# LEO_COTS_ant_tripler_rev1.net
KiCad netlist of a schematic drawn in Altium Designer
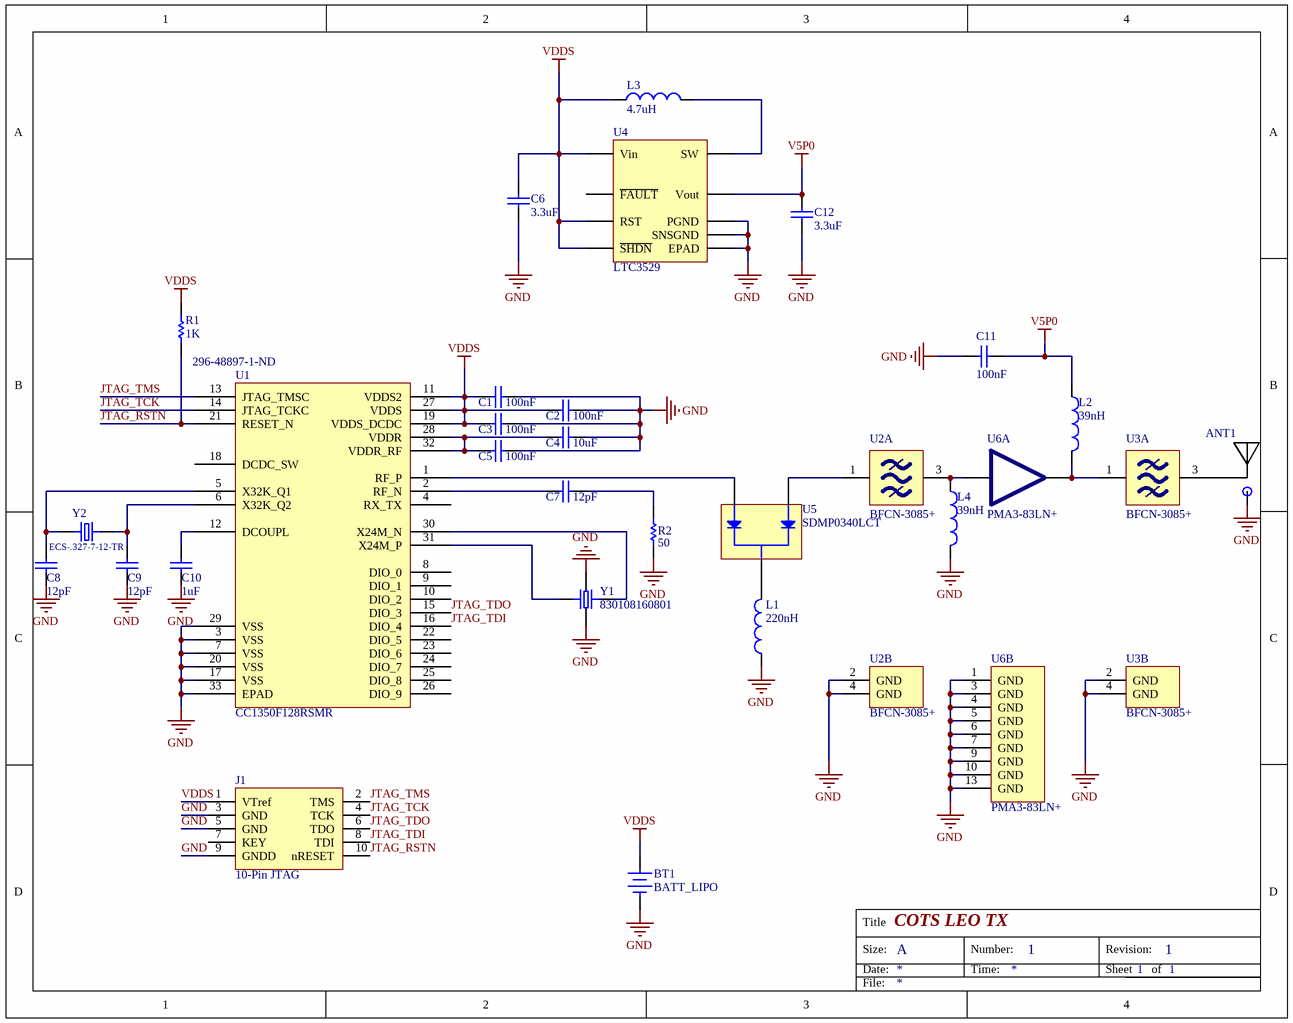
[diagram p0: LEO_COTS_ant_tripler_rev1.SchDoc]

(export (version "E")
  (design (tool "Eeschema 10.0.6"))
  (components
    (comp (ref "ANT1")
      (value "ANT")
      (footprint "RESLOOP_OD10_fw15_fl180_sw12_sl15")
      (description "PCB antenna")
      (libsource (lib "LEO_COTS_components") (part "ANT"))
    )
    (comp (ref "BT1")
      (value "BATT_LIPO")
      (footprint "LIPO_1cm_1cm")
      (libsource (lib "LEO_COTS_components") (part "BATT_LIPO"))
    )
    (comp (ref "C1")
      (value "100nF")
      (footprint "CAPC0603X04N")
      (description "CAP CER 100nF 0201")
      (fields (field (name "Comment") "CAP_0201"))
      (libsource (lib "LEO_COTS_components") (part "CAP_0201"))
    )
    (comp (ref "C2")
      (value "100nF")
      (footprint "CAPC0603X04N")
      (description "CAP CER 100nF 0201")
      (fields (field (name "Comment") "CAP_0201"))
      (libsource (lib "LEO_COTS_components") (part "CAP_0201"))
    )
    (comp (ref "C3")
      (value "100nF")
      (footprint "CAPC0603X04N")
      (description "CAP CER 100nF 0201")
      (fields (field (name "Comment") "CAP_0201"))
      (libsource (lib "LEO_COTS_components") (part "CAP_0201"))
    )
    (comp (ref "C4")
      (value "10uF")
      (footprint "CAPC1608X05N")
      (description "CAP CER 10uF 0603")
      (fields (field (name "Comment") "CAP_0603"))
      (libsource (lib "LEO_COTS_components") (part "CAP_0603"))
    )
    (comp (ref "C5")
      (value "100nF")
      (footprint "CAPC0603X04N")
      (description "CAP CER 100nF 0201")
      (fields (field (name "Comment") "CAP_0201"))
      (libsource (lib "LEO_COTS_components") (part "CAP_0201"))
    )
    (comp (ref "C6")
      (value "3.3uF")
      (footprint "CAPC1608X05N")
      (description "CAP CER 3.3uF 0603")
      (fields (field (name "Comment") "CAP_0603"))
      (libsource (lib "LEO_COTS_components") (part "CAP_0603"))
    )
    (comp (ref "C7")
      (value "12pF")
      (footprint "CAPC0603X04N")
      (description "CAP CER 12pF 0201")
      (fields (field (name "Comment") "CAP_0201"))
      (libsource (lib "LEO_COTS_components") (part "CAP_0201"))
    )
    (comp (ref "C8")
      (value "12pF")
      (footprint "CAPC0603X04N")
      (description "CAP CER 12pF 0201")
      (fields (field (name "Comment") "CAP_0201"))
      (libsource (lib "LEO_COTS_components") (part "CAP_0201"))
    )
    (comp (ref "C9")
      (value "12pF")
      (footprint "CAPC0603X04N")
      (description "CAP CER 12pF 0201")
      (fields (field (name "Comment") "CAP_0201"))
      (libsource (lib "LEO_COTS_components") (part "CAP_0201"))
    )
    (comp (ref "C10")
      (value "1uF")
      (footprint "CAPC0603X04N")
      (description "CAP CER 1uF 0201")
      (fields (field (name "Comment") "CAP_0201"))
      (libsource (lib "LEO_COTS_components") (part "CAP_0201"))
    )
    (comp (ref "C11")
      (value "100nF")
      (footprint "CAPC0603X04N")
      (description "CAP CER 100nF 0201")
      (fields (field (name "Comment") "CAP_0201"))
      (libsource (lib "LEO_COTS_components") (part "CAP_0201"))
    )
    (comp (ref "C12")
      (value "3.3uF")
      (footprint "CAPC1608X05N")
      (description "CAP CER 3.3uF 0603")
      (fields (field (name "Comment") "CAP_0603"))
      (libsource (lib "LEO_COTS_components") (part "CAP_0603"))
    )
    (comp (ref "J1")
      (value "10-Pin JTAG")
      (footprint "FTSH-105-01-F-DV-007-K")
      (description "10-pin JTAG")
      (libsource (lib "LEO_COTS_components") (part "CM10"))
    )
    (comp (ref "L1")
      (value "220nH")
      (footprint "0402")
      (description "Inductor")
      (fields (field (name "PUBLISHER") "Altium Limited"))
      (libsource (lib "") (part "Inductor_1"))
    )
    (comp (ref "L2")
      (value "39nH")
      (footprint "0402")
      (description "Inductor")
      (fields (field (name "PUBLISHER") "Altium Limited"))
      (libsource (lib "LEO_COTS_components") (part "Inductor"))
    )
    (comp (ref "L3")
      (value "4.7uH")
      (footprint "C0805")
      (description "Inductor")
      (fields (field (name "PUBLISHER") "Altium Limited"))
      (libsource (lib "LEO_COTS_components") (part "Inductor"))
    )
    (comp (ref "L4")
      (value "39nH")
      (footprint "0402")
      (description "Inductor")
      (fields (field (name "PUBLISHER") "Altium Limited"))
      (libsource (lib "LEO_COTS_components") (part "Inductor"))
    )
    (comp (ref "R1")
      (value "1K")
      (footprint "CAPC0603X04N")
      (description "RES 1K OHM 0201")
      (fields (field (name "Comment") "RES_0201") (field (name "PUBLISHER") "Altium Limited"))
      (libsource (lib "LEO_COTS_components") (part "Res Semi"))
    )
    (comp (ref "R2")
      (value "50")
      (footprint "CAPC0603X04N")
      (description "RES 50 OHM 0201")
      (fields (field (name "Comment") "RES_0201") (field (name "PUBLISHER") "Altium Limited"))
      (libsource (lib "LEO_COTS_components") (part "Res Semi"))
    )
    (comp (ref "U1")
      (value "CC1350F128RSMR")
      (footprint "QFN40P400X400X100-33N")
      (description "Ultra-Low-Power Dual-Band Wireless MCU")
      (fields (field (name "SUPPLIER PART NUMBER 1") "296-48897-1-ND"))
      (libsource (lib "LEO_COTS_components") (part "CC1350F128RSMR"))
    )
    (comp (ref "U2")
      (value "BFCN-3085+")
      (footprint "FV1206")
      (description "2800 to 3400 MHz Band-Pass Filter")
      (libsource (lib "LEO_COTS_components") (part "BFCN-3085+"))
    )
    (comp (ref "U3")
      (value "BFCN-3085+")
      (footprint "FV1206")
      (description "2800 to 3400 MHz Band-Pass Filter")
      (libsource (lib "LEO_COTS_components") (part "BFCN-3085+"))
    )
    (comp (ref "U4")
      (value "LTC3529")
      (footprint "8-DFN")
      (description "5V Boost Converter")
      (libsource (lib "LEO_COTS_components") (part "LTC3529"))
    )
    (comp (ref "U5")
      (value "SDMP0340LCT")
      (footprint "SOT-523")
      (description "Dual Common Cathode Schottky")
      (libsource (lib "LEO_COTS_components") (part "SDMP0340LCT"))
    )
    (comp (ref "U6")
      (value "PMA3-83LN+")
      (footprint "DQ1225")
      (description "Wideband LNA")
      (libsource (lib "LEO_COTS_components") (part "PMA3-83LN+"))
    )
    (comp (ref "Y1")
      (value "830108160801")
      (footprint "LFXTAL081608")
      (description "24 MHz crystal")
      (libsource (lib "LEO_COTS_components") (part "830108160801"))
    )
    (comp (ref "Y2")
      (value "ECS-.327-7-12-TR")
      (footprint "XTAL_ECS-.327-7-12-TR")
      (description "32.768 kHz SMD Crystal")
      (libsource (lib "LEO_COTS_components") (part "ECS-.327-7-12-TR"))
    )
  )
  (nets
    (net (code "1") (name "/JTAG_RSTN") (class "Default")
      (node (ref "J1") (pin "10") (pinfunction "nRESET_10") (pintype "passive"))
      (node (ref "R1") (pin "1") (pinfunction "1_1") (pintype "passive"))
      (node (ref "U1") (pin "21") (pinfunction "RESET_N_21") (pintype "passive"))
    )
    (net (code "2") (name "/JTAG_TCK") (class "Default")
      (node (ref "J1") (pin "4") (pinfunction "TCK_4") (pintype "passive"))
      (node (ref "U1") (pin "14") (pinfunction "JTAG_TCKC_14") (pintype "passive"))
    )
    (net (code "3") (name "/JTAG_TDI") (class "Default")
      (node (ref "J1") (pin "8") (pinfunction "TDI_8") (pintype "passive"))
      (node (ref "U1") (pin "16") (pinfunction "DIO_4_16") (pintype "passive"))
    )
    (net (code "4") (name "/JTAG_TDO") (class "Default")
      (node (ref "J1") (pin "6") (pinfunction "TDO_6") (pintype "passive"))
      (node (ref "U1") (pin "15") (pinfunction "DIO_3_15") (pintype "passive"))
    )
    (net (code "5") (name "/JTAG_TMS") (class "Default")
      (node (ref "J1") (pin "2") (pinfunction "TMS_2") (pintype "passive"))
      (node (ref "U1") (pin "13") (pinfunction "JTAG_TMSC_13") (pintype "passive"))
    )
    (net (code "6") (name "GND") (class "Default")
      (node (ref "ANT1") (pin "2") (pinfunction "-_2") (pintype "passive"))
      (node (ref "BT1") (pin "2") (pinfunction "-_2") (pintype "passive"))
      (node (ref "C1") (pin "1") (pinfunction "1_1") (pintype "passive"))
      (node (ref "C10") (pin "1") (pinfunction "1_1") (pintype "passive"))
      (node (ref "C11") (pin "1") (pinfunction "1_1") (pintype "passive"))
      (node (ref "C12") (pin "1") (pinfunction "1_1") (pintype "passive"))
      (node (ref "C2") (pin "1") (pinfunction "1_1") (pintype "passive"))
      (node (ref "C3") (pin "1") (pinfunction "1_1") (pintype "passive"))
      (node (ref "C4") (pin "2") (pinfunction "2_2") (pintype "passive"))
      (node (ref "C5") (pin "1") (pinfunction "1_1") (pintype "passive"))
      (node (ref "C6") (pin "1") (pinfunction "1_1") (pintype "passive"))
      (node (ref "C8") (pin "1") (pinfunction "1_1") (pintype "passive"))
      (node (ref "C9") (pin "1") (pinfunction "1_1") (pintype "passive"))
      (node (ref "J1") (pin "3") (pinfunction "GND_3") (pintype "passive"))
      (node (ref "J1") (pin "5") (pinfunction "GND_5") (pintype "passive"))
      (node (ref "J1") (pin "9") (pinfunction "GNDD_9") (pintype "passive"))
      (node (ref "L1") (pin "2") (pinfunction "2_2") (pintype "passive"))
      (node (ref "L4") (pin "2") (pinfunction "2_2") (pintype "passive"))
      (node (ref "R2") (pin "1") (pinfunction "1_1") (pintype "passive"))
      (node (ref "U1") (pin "17") (pinfunction "VSS_17") (pintype "passive"))
      (node (ref "U1") (pin "20") (pinfunction "VSS_20") (pintype "passive"))
      (node (ref "U1") (pin "29") (pinfunction "VSS_29") (pintype "passive"))
      (node (ref "U1") (pin "3") (pinfunction "VSS_3") (pintype "passive"))
      (node (ref "U1") (pin "33") (pinfunction "EPAD_33") (pintype "passive"))
      (node (ref "U1") (pin "7") (pinfunction "VSS_7") (pintype "passive"))
      (node (ref "U2") (pin "2") (pinfunction "GND_2") (pintype "tri_state"))
      (node (ref "U2") (pin "4") (pinfunction "GND_4") (pintype "tri_state"))
      (node (ref "U3") (pin "2") (pinfunction "GND_2") (pintype "tri_state"))
      (node (ref "U3") (pin "4") (pinfunction "GND_4") (pintype "tri_state"))
      (node (ref "U4") (pin "4") (pinfunction "PGND_4") (pintype "passive"))
      (node (ref "U4") (pin "6") (pinfunction "SNSGND_6") (pintype "passive"))
      (node (ref "U4") (pin "9") (pinfunction "EPAD_9") (pintype "passive"))
      (node (ref "U6") (pin "1") (pinfunction "GND_1") (pintype "tri_state"))
      (node (ref "U6") (pin "10") (pinfunction "GND_10") (pintype "tri_state"))
      (node (ref "U6") (pin "13") (pinfunction "GND_13") (pintype "tri_state"))
      (node (ref "U6") (pin "3") (pinfunction "GND_3") (pintype "tri_state"))
      (node (ref "U6") (pin "4") (pinfunction "GND_4") (pintype "tri_state"))
      (node (ref "U6") (pin "5") (pinfunction "GND_5") (pintype "tri_state"))
      (node (ref "U6") (pin "6") (pinfunction "GND_6") (pintype "tri_state"))
      (node (ref "U6") (pin "7") (pinfunction "GND_7") (pintype "tri_state"))
      (node (ref "U6") (pin "9") (pinfunction "GND_9") (pintype "tri_state"))
      (node (ref "Y1") (pin "2") (pinfunction "2_2") (pintype "passive"))
      (node (ref "Y1") (pin "4") (pinfunction "4_4") (pintype "passive"))
    )
    (net (code "7") (name "Net-(ANT1-+)") (class "Default")
      (node (ref "ANT1") (pin "1") (pinfunction "+_1") (pintype "passive"))
      (node (ref "U3") (pin "3") (pinfunction "OUT_3") (pintype "tri_state"))
    )
    (net (code "8") (name "Net-(C7-Pad1)") (class "Default")
      (node (ref "C7") (pin "1") (pinfunction "1_1") (pintype "passive"))
      (node (ref "R2") (pin "2") (pinfunction "2_2") (pintype "passive"))
    )
    (net (code "9") (name "Net-(L1-Pad1)") (class "Default")
      (node (ref "L1") (pin "1") (pinfunction "1_1") (pintype "passive"))
      (node (ref "U5") (pin "3") (pinfunction "3_3") (pintype "passive"))
    )
    (net (code "10") (name "Net-(U1-DCOUPL)") (class "Default")
      (node (ref "C10") (pin "2") (pinfunction "2_2") (pintype "passive"))
      (node (ref "U1") (pin "12") (pinfunction "DCOUPL_12") (pintype "passive"))
    )
    (net (code "11") (name "Net-(U1-RF_N)") (class "Default")
      (node (ref "C7") (pin "2") (pinfunction "2_2") (pintype "passive"))
      (node (ref "U1") (pin "2") (pinfunction "RF_N_2") (pintype "passive"))
    )
    (net (code "12") (name "Net-(U1-RF_P)") (class "Default")
      (node (ref "U1") (pin "1") (pinfunction "RF_P_1") (pintype "passive"))
      (node (ref "U5") (pin "1") (pinfunction "1_1") (pintype "passive"))
    )
    (net (code "13") (name "Net-(U1-VDDR)") (class "Default")
      (node (ref "C4") (pin "1") (pinfunction "1_1") (pintype "passive"))
      (node (ref "C5") (pin "2") (pinfunction "2_2") (pintype "passive"))
      (node (ref "U1") (pin "28") (pinfunction "VDDR_28") (pintype "passive"))
      (node (ref "U1") (pin "32") (pinfunction "VDDR_RF_32") (pintype "passive"))
    )
    (net (code "14") (name "Net-(U1-X24M_N)") (class "Default")
      (node (ref "U1") (pin "30") (pinfunction "X24M_N_30") (pintype "passive"))
      (node (ref "Y1") (pin "3") (pinfunction "3_3") (pintype "passive"))
    )
    (net (code "15") (name "Net-(U1-X24M_P)") (class "Default")
      (node (ref "U1") (pin "31") (pinfunction "X24M_P_31") (pintype "passive"))
      (node (ref "Y1") (pin "1") (pinfunction "1_1") (pintype "passive"))
    )
    (net (code "16") (name "Net-(U1-X32K_Q1)") (class "Default")
      (node (ref "C8") (pin "2") (pinfunction "2_2") (pintype "passive"))
      (node (ref "U1") (pin "5") (pinfunction "X32K_Q1_5") (pintype "passive"))
      (node (ref "Y2") (pin "1") (pinfunction "1_1") (pintype "passive"))
    )
    (net (code "17") (name "Net-(U1-X32K_Q2)") (class "Default")
      (node (ref "C9") (pin "2") (pinfunction "2_2") (pintype "passive"))
      (node (ref "U1") (pin "6") (pinfunction "X32K_Q2_6") (pintype "passive"))
      (node (ref "Y2") (pin "2") (pinfunction "2_2") (pintype "passive"))
    )
    (net (code "18") (name "Net-(U2A-IN)") (class "Default")
      (node (ref "U2") (pin "1") (pinfunction "IN_1") (pintype "tri_state"))
      (node (ref "U5") (pin "2") (pinfunction "2_2") (pintype "passive"))
    )
    (net (code "19") (name "Net-(U2A-OUT)") (class "Default")
      (node (ref "L4") (pin "1") (pinfunction "1_1") (pintype "passive"))
      (node (ref "U2") (pin "3") (pinfunction "OUT_3") (pintype "tri_state"))
      (node (ref "U6") (pin "2") (pinfunction "IN_2") (pintype "tri_state"))
    )
    (net (code "20") (name "Net-(U3A-IN)") (class "Default")
      (node (ref "L2") (pin "2") (pinfunction "2_2") (pintype "passive"))
      (node (ref "U3") (pin "1") (pinfunction "IN_1") (pintype "tri_state"))
      (node (ref "U6") (pin "8") (pinfunction "OUT_8") (pintype "tri_state"))
    )
    (net (code "21") (name "Net-(U4-SW)") (class "Default")
      (node (ref "L3") (pin "2") (pinfunction "2_2") (pintype "passive"))
      (node (ref "U4") (pin "2") (pinfunction "SW_2") (pintype "passive"))
    )
    (net (code "22") (name "V5P0") (class "Default")
      (node (ref "C11") (pin "2") (pinfunction "2_2") (pintype "passive"))
      (node (ref "C12") (pin "2") (pinfunction "2_2") (pintype "passive"))
      (node (ref "L2") (pin "1") (pinfunction "1_1") (pintype "passive"))
      (node (ref "U4") (pin "1") (pinfunction "Vout_1") (pintype "passive"))
    )
    (net (code "23") (name "VDDS") (class "Default")
      (node (ref "BT1") (pin "1") (pinfunction "+_1") (pintype "passive"))
      (node (ref "C1") (pin "2") (pinfunction "2_2") (pintype "passive"))
      (node (ref "C2") (pin "2") (pinfunction "2_2") (pintype "passive"))
      (node (ref "C3") (pin "2") (pinfunction "2_2") (pintype "passive"))
      (node (ref "C6") (pin "2") (pinfunction "2_2") (pintype "passive"))
      (node (ref "J1") (pin "1") (pinfunction "VTref_1") (pintype "passive"))
      (node (ref "L3") (pin "1") (pinfunction "1_1") (pintype "passive"))
      (node (ref "R1") (pin "2") (pinfunction "2_2") (pintype "passive"))
      (node (ref "U1") (pin "11") (pinfunction "VDDS2_11") (pintype "passive"))
      (node (ref "U1") (pin "19") (pinfunction "VDDS_DCDC_19") (pintype "passive"))
      (node (ref "U1") (pin "27") (pinfunction "VDDS_27") (pintype "passive"))
      (node (ref "U4") (pin "3") (pinfunction "~{SHDN}_3") (pintype "passive"))
      (node (ref "U4") (pin "7") (pinfunction "RST_7") (pintype "passive"))
      (node (ref "U4") (pin "8") (pinfunction "Vin_8") (pintype "passive"))
    )
    (net (code "24") (name "unconnected-(J1-KEY-Pad7)") (class "Default")
      (node (ref "J1") (pin "7") (pinfunction "KEY_7") (pintype "passive"))
    )
    (net (code "25") (name "unconnected-(U1-DCDC_SW-Pad18)") (class "Default")
      (node (ref "U1") (pin "18") (pinfunction "DCDC_SW_18") (pintype "passive"))
    )
    (net (code "26") (name "unconnected-(U1-DIO_0-Pad8)") (class "Default")
      (node (ref "U1") (pin "8") (pinfunction "DIO_0_8") (pintype "passive"))
    )
    (net (code "27") (name "unconnected-(U1-DIO_1-Pad9)") (class "Default")
      (node (ref "U1") (pin "9") (pinfunction "DIO_1_9") (pintype "passive"))
    )
    (net (code "28") (name "unconnected-(U1-DIO_2-Pad10)") (class "Default")
      (node (ref "U1") (pin "10") (pinfunction "DIO_2_10") (pintype "passive"))
    )
    (net (code "29") (name "unconnected-(U1-DIO_5-Pad22)") (class "Default")
      (node (ref "U1") (pin "22") (pinfunction "DIO_5_22") (pintype "passive"))
    )
    (net (code "30") (name "unconnected-(U1-DIO_6-Pad23)") (class "Default")
      (node (ref "U1") (pin "23") (pinfunction "DIO_6_23") (pintype "passive"))
    )
    (net (code "31") (name "unconnected-(U1-DIO_7-Pad24)") (class "Default")
      (node (ref "U1") (pin "24") (pinfunction "DIO_7_24") (pintype "passive"))
    )
    (net (code "32") (name "unconnected-(U1-DIO_8-Pad25)") (class "Default")
      (node (ref "U1") (pin "25") (pinfunction "DIO_8_25") (pintype "passive"))
    )
    (net (code "33") (name "unconnected-(U1-DIO_9-Pad26)") (class "Default")
      (node (ref "U1") (pin "26") (pinfunction "DIO_9_26") (pintype "passive"))
    )
    (net (code "34") (name "unconnected-(U1-RX_TX-Pad4)") (class "Default")
      (node (ref "U1") (pin "4") (pinfunction "RX_TX_4") (pintype "passive"))
    )
    (net (code "35") (name "unconnected-(U4-~{FAULT}-Pad5)") (class "Default")
      (node (ref "U4") (pin "5") (pinfunction "~{FAULT}_5") (pintype "passive"))
    )
  )
)
